# Redundant_Batteries.net
KiCad netlist of a schematic drawn in Altium Designer
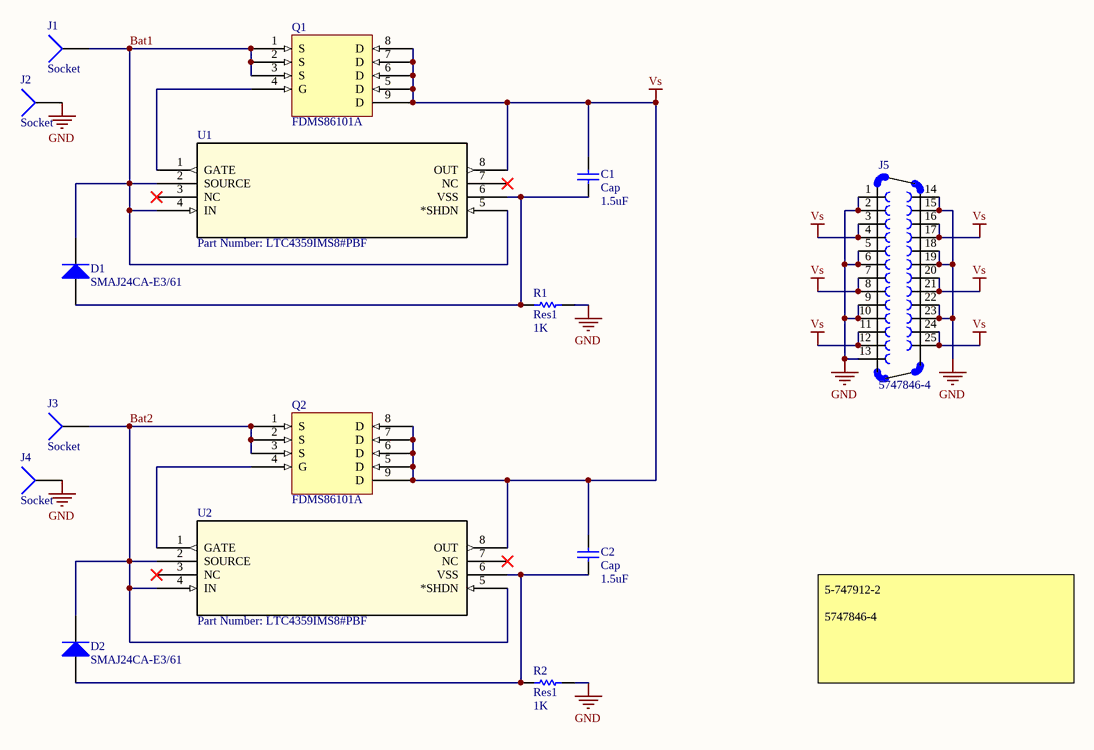
[diagram p0: Redundant Batteries.SchDoc]

(export (version "E")
  (design (tool "Eeschema 10.0.6"))
  (components
    (comp (ref "C1")
      (value "Cap")
      (footprint "C1210_M")
      (description "Capacitor")
      (fields (field (name "ALTIUM_VALUE") "1.5uF") (field (name "PUBLISHER") "Altium Limited"))
      (libsource (lib "Miscellaneous Devices") (part "Cap"))
    )
    (comp (ref "C2")
      (value "Cap")
      (footprint "C1210_M")
      (description "Capacitor")
      (fields (field (name "ALTIUM_VALUE") "1.5uF") (field (name "PUBLISHER") "Altium Limited"))
      (libsource (lib "Miscellaneous Devices") (part "Cap"))
    )
    (comp (ref "D1")
      (value "SMAJ24CA-E3/61")
      (footprint "DIODE_DO-214AC")
      (description "Default Diode")
      (fields (field (name "PUBLISHER") "Altium Limited"))
      (libsource (lib "Miscellaneous Devices") (part "Diode"))
    )
    (comp (ref "D2")
      (value "SMAJ24CA-E3/61")
      (footprint "DIODE_DO-214AC")
      (description "Default Diode")
      (fields (field (name "PUBLISHER") "Altium Limited"))
      (libsource (lib "Miscellaneous Devices") (part "Diode"))
    )
    (comp (ref "J1")
      (value "Socket")
      (footprint "PCBComponent_1")
      (fields (field (name "PUBLISHER") "Altium Limited"))
      (libsource (lib "Miscellaneous Connectors") (part "Socket"))
    )
    (comp (ref "J2")
      (value "Socket")
      (footprint "PCBComponent_1")
      (fields (field (name "PUBLISHER") "Altium Limited"))
      (libsource (lib "Miscellaneous Connectors") (part "Socket"))
    )
    (comp (ref "J3")
      (value "Socket")
      (footprint "PCBComponent_1")
      (fields (field (name "PUBLISHER") "Altium Limited"))
      (libsource (lib "Miscellaneous Connectors") (part "Socket"))
    )
    (comp (ref "J4")
      (value "Socket")
      (footprint "PCBComponent_1")
      (fields (field (name "PUBLISHER") "Altium Limited"))
      (libsource (lib "Miscellaneous Connectors") (part "Socket"))
    )
    (comp (ref "J5")
      (value "5747846-4")
      (footprint "*TE_5747846-4")
      (libsource (lib "5747846-4") (part "5747846-4"))
    )
    (comp (ref "Q1")
      (value "FDMS86101A")
      (footprint "FDMS86101A")
      (description "MOSFET N-CH 100V 13A POWER56")
      (libsource (lib "FDMS86101A") (part "FDMS86101A"))
    )
    (comp (ref "Q2")
      (value "FDMS86101A")
      (footprint "FDMS86101A")
      (description "MOSFET N-CH 100V 13A POWER56")
      (libsource (lib "FDMS86101A") (part "FDMS86101A"))
    )
    (comp (ref "R1")
      (value "Res1")
      (footprint "STA_RMCF2512")
      (description "Resistor")
      (fields (field (name "ALTIUM_VALUE") "1K") (field (name "PUBLISHER") "Altium Limited"))
      (libsource (lib "Miscellaneous Devices") (part "Res1"))
    )
    (comp (ref "R2")
      (value "Res1")
      (footprint "STA_RMCF2512")
      (description "Resistor")
      (fields (field (name "ALTIUM_VALUE") "1K") (field (name "PUBLISHER") "Altium Limited"))
      (libsource (lib "Miscellaneous Devices") (part "Res1"))
    )
    (comp (ref "U1")
      (value "Part Number: LTC4359IMS8#PBF")
      (footprint "LTC4359IMS8#PBF:MSOP-8_MS")
      (description "No Description Available")
      (fields
        (field (name "MANUFACTURER_PART_NUMBER") "LTC4359IMS8#PBF")
        (field (name "COPYRIGHT") "Copyright (C) 2018 Accelerated Designs. All rights reserved")
      )
      (libsource (lib "LTC4359IMS8#PBF") (part "LTC4359IMS8#PBF"))
    )
    (comp (ref "U2")
      (value "Part Number: LTC4359IMS8#PBF")
      (footprint "LTC4359IMS8#PBF:MSOP-8_MS")
      (description "No Description Available")
      (fields
        (field (name "MANUFACTURER_PART_NUMBER") "LTC4359IMS8#PBF")
        (field (name "COPYRIGHT") "Copyright (C) 2018 Accelerated Designs. All rights reserved")
      )
      (libsource (lib "LTC4359IMS8#PBF") (part "LTC4359IMS8#PBF"))
    )
  )
  (nets
    (net (code "1") (name "/Bat1") (class "Default")
      (node (ref "D1") (pin "2") (pinfunction "K_2") (pintype "passive"))
      (node (ref "J1") (pin "1") (pinfunction "1_1") (pintype "passive"))
      (node (ref "Q1") (pin "1") (pinfunction "S_1") (pintype "input"))
      (node (ref "Q1") (pin "2") (pinfunction "S_2") (pintype "input"))
      (node (ref "Q1") (pin "3") (pinfunction "S_3") (pintype "input"))
      (node (ref "U1") (pin "2") (pinfunction "SOURCE_2") (pintype "passive"))
      (node (ref "U1") (pin "4") (pinfunction "IN_4") (pintype "input"))
      (node (ref "U1") (pin "5") (pinfunction "*SHDN_5") (pintype "input"))
    )
    (net (code "2") (name "/Bat2") (class "Default")
      (node (ref "D2") (pin "2") (pinfunction "K_2") (pintype "passive"))
      (node (ref "J3") (pin "1") (pinfunction "1_1") (pintype "passive"))
      (node (ref "Q2") (pin "1") (pinfunction "S_1") (pintype "input"))
      (node (ref "Q2") (pin "2") (pinfunction "S_2") (pintype "input"))
      (node (ref "Q2") (pin "3") (pinfunction "S_3") (pintype "input"))
      (node (ref "U2") (pin "2") (pinfunction "SOURCE_2") (pintype "passive"))
      (node (ref "U2") (pin "4") (pinfunction "IN_4") (pintype "input"))
      (node (ref "U2") (pin "5") (pinfunction "*SHDN_5") (pintype "input"))
    )
    (net (code "3") (name "GND") (class "Default")
      (node (ref "J2") (pin "1") (pinfunction "1_1") (pintype "passive"))
      (node (ref "J4") (pin "1") (pinfunction "1_1") (pintype "passive"))
      (node (ref "J5") (pin "1") (pinfunction "1_1") (pintype "passive"))
      (node (ref "J5") (pin "10") (pinfunction "10_10") (pintype "passive"))
      (node (ref "J5") (pin "13") (pinfunction "13_13") (pintype "passive"))
      (node (ref "J5") (pin "14") (pinfunction "14_14") (pintype "passive"))
      (node (ref "J5") (pin "15") (pinfunction "15_15") (pintype "passive"))
      (node (ref "J5") (pin "18") (pinfunction "18_18") (pintype "passive"))
      (node (ref "J5") (pin "19") (pinfunction "19_19") (pintype "passive"))
      (node (ref "J5") (pin "2") (pinfunction "2_2") (pintype "passive"))
      (node (ref "J5") (pin "22") (pinfunction "22_22") (pintype "passive"))
      (node (ref "J5") (pin "23") (pinfunction "23_23") (pintype "passive"))
      (node (ref "J5") (pin "5") (pinfunction "5_5") (pintype "passive"))
      (node (ref "J5") (pin "6") (pinfunction "6_6") (pintype "passive"))
      (node (ref "J5") (pin "9") (pinfunction "9_9") (pintype "passive"))
      (node (ref "R1") (pin "2") (pinfunction "2_2") (pintype "passive"))
      (node (ref "R2") (pin "2") (pinfunction "2_2") (pintype "passive"))
    )
    (net (code "4") (name "Net-(D1-A)") (class "Default")
      (node (ref "C1") (pin "1") (pinfunction "1_1") (pintype "passive"))
      (node (ref "D1") (pin "1") (pinfunction "A_1") (pintype "passive"))
      (node (ref "R1") (pin "1") (pinfunction "1_1") (pintype "passive"))
      (node (ref "U1") (pin "6") (pinfunction "VSS_6") (pintype "power_in"))
    )
    (net (code "5") (name "Net-(D2-A)") (class "Default")
      (node (ref "C2") (pin "1") (pinfunction "1_1") (pintype "passive"))
      (node (ref "D2") (pin "1") (pinfunction "A_1") (pintype "passive"))
      (node (ref "R2") (pin "1") (pinfunction "1_1") (pintype "passive"))
      (node (ref "U2") (pin "6") (pinfunction "VSS_6") (pintype "power_in"))
    )
    (net (code "6") (name "Net-(Q1-G)") (class "Default")
      (node (ref "Q1") (pin "4") (pinfunction "G_4") (pintype "input"))
      (node (ref "U1") (pin "1") (pinfunction "GATE_1") (pintype "output"))
    )
    (net (code "7") (name "Net-(Q2-G)") (class "Default")
      (node (ref "Q2") (pin "4") (pinfunction "G_4") (pintype "input"))
      (node (ref "U2") (pin "1") (pinfunction "GATE_1") (pintype "output"))
    )
    (net (code "8") (name "Vs") (class "Default")
      (node (ref "C1") (pin "2") (pinfunction "2_2") (pintype "passive"))
      (node (ref "C2") (pin "2") (pinfunction "2_2") (pintype "passive"))
      (node (ref "J5") (pin "11") (pinfunction "11_11") (pintype "passive"))
      (node (ref "J5") (pin "12") (pinfunction "12_12") (pintype "passive"))
      (node (ref "J5") (pin "16") (pinfunction "16_16") (pintype "passive"))
      (node (ref "J5") (pin "17") (pinfunction "17_17") (pintype "passive"))
      (node (ref "J5") (pin "20") (pinfunction "20_20") (pintype "passive"))
      (node (ref "J5") (pin "21") (pinfunction "21_21") (pintype "passive"))
      (node (ref "J5") (pin "24") (pinfunction "24_24") (pintype "passive"))
      (node (ref "J5") (pin "25") (pinfunction "25_25") (pintype "passive"))
      (node (ref "J5") (pin "3") (pinfunction "3_3") (pintype "passive"))
      (node (ref "J5") (pin "4") (pinfunction "4_4") (pintype "passive"))
      (node (ref "J5") (pin "7") (pinfunction "7_7") (pintype "passive"))
      (node (ref "J5") (pin "8") (pinfunction "8_8") (pintype "passive"))
      (node (ref "Q1") (pin "5") (pinfunction "D_5") (pintype "input"))
      (node (ref "Q1") (pin "6") (pinfunction "D_6") (pintype "input"))
      (node (ref "Q1") (pin "7") (pinfunction "D_7") (pintype "input"))
      (node (ref "Q1") (pin "8") (pinfunction "D_8") (pintype "input"))
      (node (ref "Q1") (pin "9") (pinfunction "D_9") (pintype "passive"))
      (node (ref "Q2") (pin "5") (pinfunction "D_5") (pintype "input"))
      (node (ref "Q2") (pin "6") (pinfunction "D_6") (pintype "input"))
      (node (ref "Q2") (pin "7") (pinfunction "D_7") (pintype "input"))
      (node (ref "Q2") (pin "8") (pinfunction "D_8") (pintype "input"))
      (node (ref "Q2") (pin "9") (pinfunction "D_9") (pintype "passive"))
      (node (ref "U1") (pin "8") (pinfunction "OUT_8") (pintype "output"))
      (node (ref "U2") (pin "8") (pinfunction "OUT_8") (pintype "output"))
    )
    (net (code "9") (name "unconnected-(U1-NC-Pad3)") (class "Default")
      (node (ref "U1") (pin "3") (pinfunction "NC_3") (pintype "passive+no_connect"))
    )
    (net (code "10") (name "unconnected-(U1-NC-Pad7)") (class "Default")
      (node (ref "U1") (pin "7") (pinfunction "NC_7") (pintype "passive+no_connect"))
    )
    (net (code "11") (name "unconnected-(U2-NC-Pad3)") (class "Default")
      (node (ref "U2") (pin "3") (pinfunction "NC_3") (pintype "passive+no_connect"))
    )
    (net (code "12") (name "unconnected-(U2-NC-Pad7)") (class "Default")
      (node (ref "U2") (pin "7") (pinfunction "NC_7") (pintype "passive+no_connect"))
    )
  )
)
